# SPinner.net
KiCad netlist of a schematic drawn in EAGLE
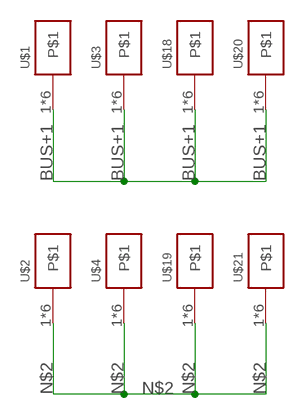
[diagram p0: schematic, sheet 1]

(export (version "E")
  (design (tool "Eeschema 10.0.6"))
  (components
    (comp (ref "U$1")
      (value "KCONNECT")
      (footprint "eagle-import:KCONNECT")
      (libsource (lib "eagle-import") (part "KCONNECT"))
    )
    (comp (ref "U$2")
      (value "KCONNECT")
      (footprint "eagle-import:KCONNECT")
      (libsource (lib "eagle-import") (part "KCONNECT"))
    )
    (comp (ref "U$3")
      (value "KCONNECT")
      (footprint "eagle-import:KCONNECT")
      (libsource (lib "eagle-import") (part "KCONNECT"))
    )
    (comp (ref "U$4")
      (value "KCONNECT")
      (footprint "eagle-import:KCONNECT")
      (libsource (lib "eagle-import") (part "KCONNECT"))
    )
    (comp (ref "U$18")
      (value "KCONNECT")
      (footprint "eagle-import:KCONNECT")
      (libsource (lib "eagle-import") (part "KCONNECT"))
    )
    (comp (ref "U$19")
      (value "KCONNECT")
      (footprint "eagle-import:KCONNECT")
      (libsource (lib "eagle-import") (part "KCONNECT"))
    )
    (comp (ref "U$20")
      (value "KCONNECT")
      (footprint "eagle-import:KCONNECT")
      (libsource (lib "eagle-import") (part "KCONNECT"))
    )
    (comp (ref "U$21")
      (value "KCONNECT")
      (footprint "eagle-import:KCONNECT")
      (libsource (lib "eagle-import") (part "KCONNECT"))
    )
  )
  (nets
    (net (code "1") (name "/BUS+1") (class "Default")
      (node (ref "U$1") (pin "1") (pinfunction "P$1_1") (pintype "bidirectional"))
      (node (ref "U$1") (pin "2") (pinfunction "P$1_2") (pintype "bidirectional"))
      (node (ref "U$1") (pin "3") (pinfunction "P$1_3") (pintype "bidirectional"))
      (node (ref "U$1") (pin "4") (pinfunction "P$1_4") (pintype "bidirectional"))
      (node (ref "U$1") (pin "P$1") (pinfunction "P$1_P$1") (pintype "bidirectional"))
      (node (ref "U$1") (pin "P$2") (pinfunction "P$1_P$2") (pintype "bidirectional"))
      (node (ref "U$18") (pin "1") (pinfunction "P$1_1") (pintype "bidirectional"))
      (node (ref "U$18") (pin "2") (pinfunction "P$1_2") (pintype "bidirectional"))
      (node (ref "U$18") (pin "3") (pinfunction "P$1_3") (pintype "bidirectional"))
      (node (ref "U$18") (pin "4") (pinfunction "P$1_4") (pintype "bidirectional"))
      (node (ref "U$18") (pin "P$1") (pinfunction "P$1_P$1") (pintype "bidirectional"))
      (node (ref "U$18") (pin "P$2") (pinfunction "P$1_P$2") (pintype "bidirectional"))
      (node (ref "U$20") (pin "1") (pinfunction "P$1_1") (pintype "bidirectional"))
      (node (ref "U$20") (pin "2") (pinfunction "P$1_2") (pintype "bidirectional"))
      (node (ref "U$20") (pin "3") (pinfunction "P$1_3") (pintype "bidirectional"))
      (node (ref "U$20") (pin "4") (pinfunction "P$1_4") (pintype "bidirectional"))
      (node (ref "U$20") (pin "P$1") (pinfunction "P$1_P$1") (pintype "bidirectional"))
      (node (ref "U$20") (pin "P$2") (pinfunction "P$1_P$2") (pintype "bidirectional"))
      (node (ref "U$3") (pin "1") (pinfunction "P$1_1") (pintype "bidirectional"))
      (node (ref "U$3") (pin "2") (pinfunction "P$1_2") (pintype "bidirectional"))
      (node (ref "U$3") (pin "3") (pinfunction "P$1_3") (pintype "bidirectional"))
      (node (ref "U$3") (pin "4") (pinfunction "P$1_4") (pintype "bidirectional"))
      (node (ref "U$3") (pin "P$1") (pinfunction "P$1_P$1") (pintype "bidirectional"))
      (node (ref "U$3") (pin "P$2") (pinfunction "P$1_P$2") (pintype "bidirectional"))
    )
    (net (code "2") (name "/N$2") (class "Default")
      (node (ref "U$19") (pin "1") (pinfunction "P$1_1") (pintype "bidirectional"))
      (node (ref "U$19") (pin "2") (pinfunction "P$1_2") (pintype "bidirectional"))
      (node (ref "U$19") (pin "3") (pinfunction "P$1_3") (pintype "bidirectional"))
      (node (ref "U$19") (pin "4") (pinfunction "P$1_4") (pintype "bidirectional"))
      (node (ref "U$19") (pin "P$1") (pinfunction "P$1_P$1") (pintype "bidirectional"))
      (node (ref "U$19") (pin "P$2") (pinfunction "P$1_P$2") (pintype "bidirectional"))
      (node (ref "U$2") (pin "1") (pinfunction "P$1_1") (pintype "bidirectional"))
      (node (ref "U$2") (pin "2") (pinfunction "P$1_2") (pintype "bidirectional"))
      (node (ref "U$2") (pin "3") (pinfunction "P$1_3") (pintype "bidirectional"))
      (node (ref "U$2") (pin "4") (pinfunction "P$1_4") (pintype "bidirectional"))
      (node (ref "U$2") (pin "P$1") (pinfunction "P$1_P$1") (pintype "bidirectional"))
      (node (ref "U$2") (pin "P$2") (pinfunction "P$1_P$2") (pintype "bidirectional"))
      (node (ref "U$21") (pin "1") (pinfunction "P$1_1") (pintype "bidirectional"))
      (node (ref "U$21") (pin "2") (pinfunction "P$1_2") (pintype "bidirectional"))
      (node (ref "U$21") (pin "3") (pinfunction "P$1_3") (pintype "bidirectional"))
      (node (ref "U$21") (pin "4") (pinfunction "P$1_4") (pintype "bidirectional"))
      (node (ref "U$21") (pin "P$1") (pinfunction "P$1_P$1") (pintype "bidirectional"))
      (node (ref "U$21") (pin "P$2") (pinfunction "P$1_P$2") (pintype "bidirectional"))
      (node (ref "U$4") (pin "1") (pinfunction "P$1_1") (pintype "bidirectional"))
      (node (ref "U$4") (pin "2") (pinfunction "P$1_2") (pintype "bidirectional"))
      (node (ref "U$4") (pin "3") (pinfunction "P$1_3") (pintype "bidirectional"))
      (node (ref "U$4") (pin "4") (pinfunction "P$1_4") (pintype "bidirectional"))
      (node (ref "U$4") (pin "P$1") (pinfunction "P$1_P$1") (pintype "bidirectional"))
      (node (ref "U$4") (pin "P$2") (pinfunction "P$1_P$2") (pintype "bidirectional"))
    )
  )
)
